# mini_controller_m328.net
KiCad netlist of a schematic drawn in EAGLE
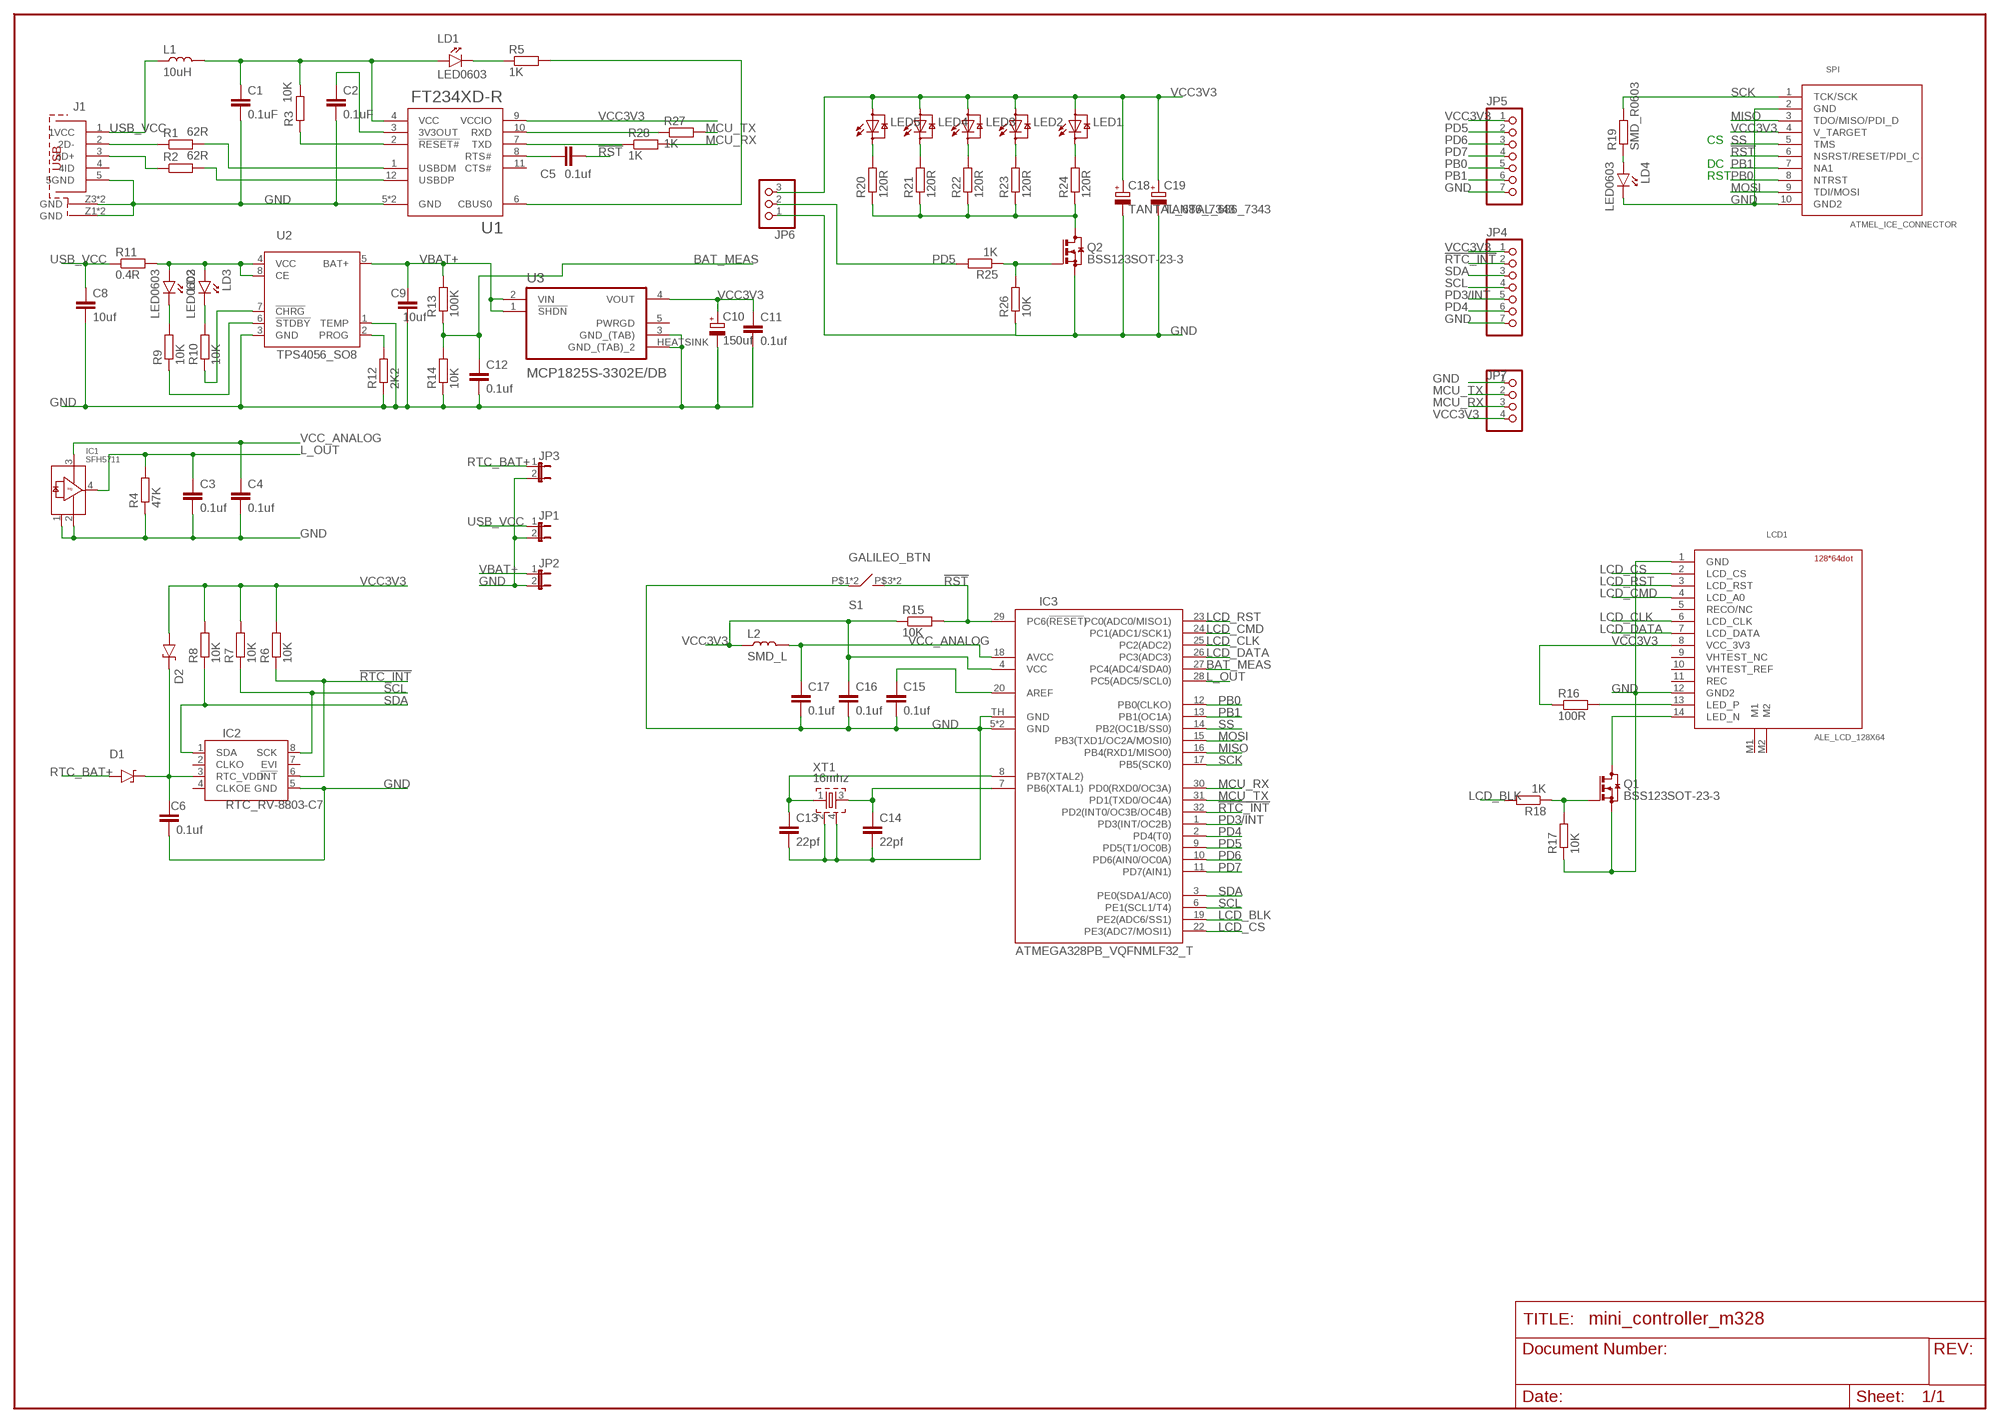
[diagram p0: schematic, sheet 1]

(export (version "E")
  (design (tool "Eeschema 10.0.6"))
  (components
    (comp (ref "C1")
      (value "0.1uF")
      (footprint "eagle-import:0603")
      (libsource (lib "eagle-import") (part "SMD_C0603"))
    )
    (comp (ref "C2")
      (value "0.1uF")
      (footprint "eagle-import:0603")
      (libsource (lib "eagle-import") (part "SMD_C0603"))
    )
    (comp (ref "C3")
      (value "0.1uf")
      (footprint "eagle-import:0603")
      (libsource (lib "eagle-import") (part "SMD_C0603"))
    )
    (comp (ref "C4")
      (value "0.1uf")
      (footprint "eagle-import:0603")
      (libsource (lib "eagle-import") (part "SMD_C0603"))
    )
    (comp (ref "C5")
      (value "0.1uf")
      (footprint "eagle-import:0603")
      (libsource (lib "eagle-import") (part "SMD_C0603"))
    )
    (comp (ref "C6")
      (value "0.1uf")
      (footprint "eagle-import:0603")
      (libsource (lib "eagle-import") (part "SMD_C0603"))
    )
    (comp (ref "C8")
      (value "10uf")
      (footprint "eagle-import:1206")
      (libsource (lib "eagle-import") (part "SMD_C1206"))
    )
    (comp (ref "C9")
      (value "10uf")
      (footprint "eagle-import:1206")
      (libsource (lib "eagle-import") (part "SMD_C1206"))
    )
    (comp (ref "C10")
      (value "150uf")
      (footprint "eagle-import:KA-3528ASYC")
      (libsource (lib "eagle-import") (part "TANTAL_150UF_3528"))
    )
    (comp (ref "C11")
      (value "0.1uf")
      (footprint "eagle-import:0603")
      (libsource (lib "eagle-import") (part "SMD_C0603"))
    )
    (comp (ref "C12")
      (value "0.1uf")
      (footprint "eagle-import:0603")
      (libsource (lib "eagle-import") (part "SMD_C0603"))
    )
    (comp (ref "C13")
      (value "22pf")
      (footprint "eagle-import:0603")
      (libsource (lib "eagle-import") (part "SMD_C0603"))
    )
    (comp (ref "C14")
      (value "22pf")
      (footprint "eagle-import:0603")
      (libsource (lib "eagle-import") (part "SMD_C0603"))
    )
    (comp (ref "C15")
      (value "0.1uf")
      (footprint "eagle-import:0603")
      (libsource (lib "eagle-import") (part "SMD_C0603"))
    )
    (comp (ref "C16")
      (value "0.1uf")
      (footprint "eagle-import:0603")
      (libsource (lib "eagle-import") (part "SMD_C0603"))
    )
    (comp (ref "C17")
      (value "0.1uf")
      (footprint "eagle-import:0603")
      (libsource (lib "eagle-import") (part "SMD_C0603"))
    )
    (comp (ref "C18")
      (value "TANTAL_686_7343")
      (footprint "eagle-import:D_7343-31R")
      (libsource (lib "eagle-import") (part "TANTAL_686_7343"))
    )
    (comp (ref "C19")
      (value "TANTAL_686_7343")
      (footprint "eagle-import:D_7343-31R")
      (libsource (lib "eagle-import") (part "TANTAL_686_7343"))
    )
    (comp (ref "D1")
      (value "D_SOD323")
      (footprint "eagle-import:SOD-323_D")
      (libsource (lib "eagle-import") (part "D_SOD323"))
    )
    (comp (ref "D2")
      (value "D_SOD323")
      (footprint "eagle-import:SOD-323_D")
      (libsource (lib "eagle-import") (part "D_SOD323"))
    )
    (comp (ref "IC1")
      (value "SFH5711")
      (footprint "eagle-import:SFH5711")
      (fields (field (name "MF") "OSRAM Opto"))
      (libsource (lib "eagle-import") (part "SFH5711"))
    )
    (comp (ref "IC2")
      (value "RTC_RV-8803-C7")
      (footprint "eagle-import:C7_RTC")
      (libsource (lib "eagle-import") (part "RTC_RV-8803-C7"))
    )
    (comp (ref "IC3")
      (value "ATMEGA328PB_VQFNMLF32_T")
      (footprint "eagle-import:MLF32-TH")
      (libsource (lib "eagle-import") (part "ATMEGA328PB_VQFNMLF32_T"))
    )
    (comp (ref "J1")
      (value "MINI_USB_TYP_B_@")
      (footprint "eagle-import:65100516121")
      (libsource (lib "eagle-import") (part "MINI_USB_TYP_B_@"))
    )
    (comp (ref "JP1")
      (value "JP1E")
      (footprint "eagle-import:JP1")
      (libsource (lib "eagle-import") (part "JP1E"))
    )
    (comp (ref "JP2")
      (value "JP1E")
      (footprint "eagle-import:JP1")
      (libsource (lib "eagle-import") (part "JP1E"))
    )
    (comp (ref "JP3")
      (value "JP1E")
      (footprint "eagle-import:JP1")
      (libsource (lib "eagle-import") (part "JP1E"))
    )
    (comp (ref "JP4")
      (value "PINHD-1X7")
      (footprint "eagle-import:1X07")
      (libsource (lib "eagle-import") (part "PINHD-1X7"))
    )
    (comp (ref "JP5")
      (value "PINHD-1X7")
      (footprint "eagle-import:1X07")
      (libsource (lib "eagle-import") (part "PINHD-1X7"))
    )
    (comp (ref "JP6")
      (value "PINHD-1X3")
      (footprint "eagle-import:1X03")
      (libsource (lib "eagle-import") (part "PINHD-1X3"))
    )
    (comp (ref "JP7")
      (value "PINHD-1X4")
      (footprint "eagle-import:1X04")
      (libsource (lib "eagle-import") (part "PINHD-1X4"))
    )
    (comp (ref "L1")
      (value "10uH")
      (footprint "eagle-import:0805")
      (libsource (lib "eagle-import") (part "SMD_L"))
    )
    (comp (ref "L2")
      (value "SMD_L")
      (footprint "eagle-import:0805")
      (libsource (lib "eagle-import") (part "SMD_L"))
    )
    (comp (ref "LCD1")
      (value "ALE_LCD_128X64")
      (footprint "eagle-import:ALE_LCD_14PIN_CONNECTOR")
      (libsource (lib "eagle-import") (part "ALE_LCD_128X64"))
    )
    (comp (ref "LD1")
      (value "LED0603")
      (footprint "eagle-import:0603_P")
      (libsource (lib "eagle-import") (part "LED0603"))
    )
    (comp (ref "LD2")
      (value "LED0603")
      (footprint "eagle-import:0603_P")
      (libsource (lib "eagle-import") (part "LED0603"))
    )
    (comp (ref "LD3")
      (value "LED0603")
      (footprint "eagle-import:0603_P")
      (libsource (lib "eagle-import") (part "LED0603"))
    )
    (comp (ref "LD4")
      (value "LED0603")
      (footprint "eagle-import:0603_P")
      (libsource (lib "eagle-import") (part "LED0603"))
    )
    (comp (ref "LED1")
      (value "GM5BW96385A")
      (footprint "eagle-import:GM5BW96385A")
      (libsource (lib "eagle-import") (part "GM5BW96385A"))
    )
    (comp (ref "LED2")
      (value "GM5BW96385A")
      (footprint "eagle-import:GM5BW96385A")
      (libsource (lib "eagle-import") (part "GM5BW96385A"))
    )
    (comp (ref "LED3")
      (value "GM5BW96385A")
      (footprint "eagle-import:GM5BW96385A")
      (libsource (lib "eagle-import") (part "GM5BW96385A"))
    )
    (comp (ref "LED4")
      (value "GM5BW96385A")
      (footprint "eagle-import:GM5BW96385A")
      (libsource (lib "eagle-import") (part "GM5BW96385A"))
    )
    (comp (ref "LED5")
      (value "GM5BW96385A")
      (footprint "eagle-import:GM5BW96385A")
      (libsource (lib "eagle-import") (part "GM5BW96385A"))
    )
    (comp (ref "Q1")
      (value "BSS123SOT-23-3")
      (footprint "eagle-import:SOT-23(3)")
      (libsource (lib "eagle-import") (part "BSS123SOT-23-3"))
    )
    (comp (ref "Q2")
      (value "BSS123SOT-23-3")
      (footprint "eagle-import:SOT-23(3)")
      (libsource (lib "eagle-import") (part "BSS123SOT-23-3"))
    )
    (comp (ref "R1")
      (value "62R")
      (footprint "eagle-import:0603")
      (libsource (lib "eagle-import") (part "SMD_R0603"))
    )
    (comp (ref "R2")
      (value "62R")
      (footprint "eagle-import:0603")
      (libsource (lib "eagle-import") (part "SMD_R0603"))
    )
    (comp (ref "R3")
      (value "10K")
      (footprint "eagle-import:0603")
      (libsource (lib "eagle-import") (part "SMD_R0603"))
    )
    (comp (ref "R4")
      (value "47K")
      (footprint "eagle-import:0603")
      (libsource (lib "eagle-import") (part "SMD_R0603"))
    )
    (comp (ref "R5")
      (value "1K")
      (footprint "eagle-import:0603")
      (libsource (lib "eagle-import") (part "SMD_R0603"))
    )
    (comp (ref "R6")
      (value "10K")
      (footprint "eagle-import:0603")
      (libsource (lib "eagle-import") (part "SMD_R0603"))
    )
    (comp (ref "R7")
      (value "10K")
      (footprint "eagle-import:0603")
      (libsource (lib "eagle-import") (part "SMD_R0603"))
    )
    (comp (ref "R8")
      (value "10K")
      (footprint "eagle-import:0603")
      (libsource (lib "eagle-import") (part "SMD_R0603"))
    )
    (comp (ref "R9")
      (value "10K")
      (footprint "eagle-import:0603")
      (libsource (lib "eagle-import") (part "SMD_R0603"))
    )
    (comp (ref "R10")
      (value "10K")
      (footprint "eagle-import:0603")
      (libsource (lib "eagle-import") (part "SMD_R0603"))
    )
    (comp (ref "R11")
      (value "0.4R")
      (footprint "eagle-import:1206")
      (libsource (lib "eagle-import") (part "SMD_R1206"))
    )
    (comp (ref "R12")
      (value "2K2")
      (footprint "eagle-import:0603")
      (libsource (lib "eagle-import") (part "SMD_R0603"))
    )
    (comp (ref "R13")
      (value "100K")
      (footprint "eagle-import:0603")
      (libsource (lib "eagle-import") (part "SMD_R0603"))
    )
    (comp (ref "R14")
      (value "10K")
      (footprint "eagle-import:0603")
      (libsource (lib "eagle-import") (part "SMD_R0603"))
    )
    (comp (ref "R15")
      (value "10K")
      (footprint "eagle-import:0603")
      (libsource (lib "eagle-import") (part "SMD_R0603"))
    )
    (comp (ref "R16")
      (value "100R")
      (footprint "eagle-import:0603")
      (libsource (lib "eagle-import") (part "SMD_R0603"))
    )
    (comp (ref "R17")
      (value "10K")
      (footprint "eagle-import:0603")
      (libsource (lib "eagle-import") (part "SMD_R0603"))
    )
    (comp (ref "R18")
      (value "1K")
      (footprint "eagle-import:0603")
      (libsource (lib "eagle-import") (part "SMD_R0603"))
    )
    (comp (ref "R19")
      (value "SMD_R0603")
      (footprint "eagle-import:0603")
      (libsource (lib "eagle-import") (part "SMD_R0603"))
    )
    (comp (ref "R20")
      (value "120R")
      (footprint "eagle-import:1206")
      (libsource (lib "eagle-import") (part "SMD_R1206"))
    )
    (comp (ref "R21")
      (value "120R")
      (footprint "eagle-import:1206")
      (libsource (lib "eagle-import") (part "SMD_R1206"))
    )
    (comp (ref "R22")
      (value "120R")
      (footprint "eagle-import:1206")
      (libsource (lib "eagle-import") (part "SMD_R1206"))
    )
    (comp (ref "R23")
      (value "120R")
      (footprint "eagle-import:1206")
      (libsource (lib "eagle-import") (part "SMD_R1206"))
    )
    (comp (ref "R24")
      (value "120R")
      (footprint "eagle-import:1206")
      (libsource (lib "eagle-import") (part "SMD_R1206"))
    )
    (comp (ref "R25")
      (value "1K")
      (footprint "eagle-import:0603")
      (libsource (lib "eagle-import") (part "SMD_R0603"))
    )
    (comp (ref "R26")
      (value "10K")
      (footprint "eagle-import:0603")
      (libsource (lib "eagle-import") (part "SMD_R0603"))
    )
    (comp (ref "R27")
      (value "1K")
      (footprint "eagle-import:0603")
      (libsource (lib "eagle-import") (part "SMD_R0603"))
    )
    (comp (ref "R28")
      (value "1K")
      (footprint "eagle-import:0603")
      (libsource (lib "eagle-import") (part "SMD_R0603"))
    )
    (comp (ref "S1")
      (value "GALILEO_BTN")
      (footprint "eagle-import:GALILEO_VERT_BTN")
      (libsource (lib "eagle-import") (part "GALILEO_BTN"))
    )
    (comp (ref "SPI")
      (value "ATMEL_ICE_CONNECTOR")
      (footprint "eagle-import:MINI10P_SPI_JTAG_PDI")
      (libsource (lib "eagle-import") (part "ATMEL_ICE_CONNECTOR"))
    )
    (comp (ref "U1")
      (value "FT234XD-R")
      (footprint "eagle-import:IC_FT234XD-R")
      (fields (field (name "MF") "FTDI,"))
      (libsource (lib "eagle-import") (part "FT234XD-R"))
    )
    (comp (ref "U2")
      (value "TPS4056_SO8")
      (footprint "eagle-import:SO8")
      (libsource (lib "eagle-import") (part "TPS4056_SO8"))
    )
    (comp (ref "U3")
      (value "MCP1825S-3302E/DB")
      (footprint "eagle-import:SOT230P700X180-4N")
      (fields (field (name "MF") "Microchip"))
      (libsource (lib "eagle-import") (part "MCP1825S-3302E/DB"))
    )
    (comp (ref "XT1")
      (value "16mhz")
      (footprint "eagle-import:QUARTZ_3X3MM")
      (libsource (lib "eagle-import") (part "QUARTZ_ZQ"))
    )
  )
  (nets
    (net (code "1") (name "/BAT_MEAS") (class "Default")
      (node (ref "C12") (pin "1") (pinfunction "1_1") (pintype "passive"))
      (node (ref "IC3") (pin "27") (pinfunction "PC4(ADC4/SDA0)_27") (pintype "bidirectional"))
      (node (ref "R13") (pin "1") (pinfunction "1_1") (pintype "passive"))
      (node (ref "R14") (pin "2") (pinfunction "2_2") (pintype "passive"))
    )
    (net (code "2") (name "/GND") (class "Default")
      (node (ref "C1") (pin "2") (pinfunction "2_2") (pintype "passive"))
      (node (ref "C10") (pin "M") (pinfunction "-_M") (pintype "passive"))
      (node (ref "C11") (pin "2") (pinfunction "2_2") (pintype "passive"))
      (node (ref "C12") (pin "2") (pinfunction "2_2") (pintype "passive"))
      (node (ref "C13") (pin "2") (pinfunction "2_2") (pintype "passive"))
      (node (ref "C14") (pin "2") (pinfunction "2_2") (pintype "passive"))
      (node (ref "C15") (pin "2") (pinfunction "2_2") (pintype "passive"))
      (node (ref "C16") (pin "2") (pinfunction "2_2") (pintype "passive"))
      (node (ref "C17") (pin "2") (pinfunction "2_2") (pintype "passive"))
      (node (ref "C18") (pin "-") (pinfunction "-_-") (pintype "passive"))
      (node (ref "C19") (pin "-") (pinfunction "-_-") (pintype "passive"))
      (node (ref "C2") (pin "2") (pinfunction "2_2") (pintype "passive"))
      (node (ref "C3") (pin "2") (pinfunction "2_2") (pintype "passive"))
      (node (ref "C4") (pin "2") (pinfunction "2_2") (pintype "passive"))
      (node (ref "C6") (pin "2") (pinfunction "2_2") (pintype "passive"))
      (node (ref "C8") (pin "2") (pinfunction "2_2") (pintype "passive"))
      (node (ref "C9") (pin "2") (pinfunction "2_2") (pintype "passive"))
      (node (ref "IC1") (pin "1") (pinfunction "1_1") (pintype "bidirectional"))
      (node (ref "IC1") (pin "2") (pinfunction "2_2") (pintype "bidirectional"))
      (node (ref "IC2") (pin "5") (pinfunction "GND_5") (pintype "bidirectional"))
      (node (ref "IC3") (pin "21") (pinfunction "GND_21") (pintype "power_in"))
      (node (ref "IC3") (pin "5") (pinfunction "GND_5") (pintype "power_in"))
      (node (ref "IC3") (pin "TH") (pinfunction "GND_TH") (pintype "power_in"))
      (node (ref "J1") (pin "5") (pinfunction "5GND_5") (pintype "passive"))
      (node (ref "J1") (pin "Z1") (pinfunction "GND_Z1") (pintype "bidirectional"))
      (node (ref "J1") (pin "Z2") (pinfunction "GND_Z2") (pintype "bidirectional"))
      (node (ref "J1") (pin "Z3") (pinfunction "GND_Z3") (pintype "bidirectional"))
      (node (ref "J1") (pin "Z4") (pinfunction "GND_Z4") (pintype "bidirectional"))
      (node (ref "JP1") (pin "2") (pinfunction "2_2") (pintype "passive"))
      (node (ref "JP2") (pin "2") (pinfunction "2_2") (pintype "passive"))
      (node (ref "JP3") (pin "2") (pinfunction "2_2") (pintype "passive"))
      (node (ref "JP4") (pin "7") (pinfunction "7_7") (pintype "passive"))
      (node (ref "JP5") (pin "7") (pinfunction "7_7") (pintype "passive"))
      (node (ref "JP6") (pin "1") (pinfunction "1_1") (pintype "passive"))
      (node (ref "JP7") (pin "1") (pinfunction "1_1") (pintype "passive"))
      (node (ref "LCD1") (pin "1") (pinfunction "GND_1") (pintype "bidirectional"))
      (node (ref "LCD1") (pin "12") (pinfunction "GND2_12") (pintype "bidirectional"))
      (node (ref "LD4") (pin "1") (pinfunction "K_1") (pintype "bidirectional"))
      (node (ref "Q1") (pin "2") (pinfunction "S_2") (pintype "passive"))
      (node (ref "Q2") (pin "2") (pinfunction "S_2") (pintype "passive"))
      (node (ref "R12") (pin "1") (pinfunction "1_1") (pintype "passive"))
      (node (ref "R14") (pin "1") (pinfunction "1_1") (pintype "passive"))
      (node (ref "R17") (pin "1") (pinfunction "1_1") (pintype "passive"))
      (node (ref "R26") (pin "1") (pinfunction "1_1") (pintype "passive"))
      (node (ref "R4") (pin "1") (pinfunction "1_1") (pintype "passive"))
      (node (ref "S1") (pin "P$1") (pinfunction "1_P$1") (pintype "bidirectional"))
      (node (ref "S1") (pin "P$2") (pinfunction "1_P$2") (pintype "bidirectional"))
      (node (ref "SPI") (pin "10") (pinfunction "GND2_10") (pintype "bidirectional"))
      (node (ref "SPI") (pin "2") (pinfunction "GND_2") (pintype "bidirectional"))
      (node (ref "U1") (pin "13") (pinfunction "GND_13") (pintype "power_in"))
      (node (ref "U1") (pin "5") (pinfunction "GND_5") (pintype "power_in"))
      (node (ref "U2") (pin "1") (pinfunction "TEMP_1") (pintype "bidirectional"))
      (node (ref "U2") (pin "3") (pinfunction "GND_3") (pintype "bidirectional"))
      (node (ref "U3") (pin "3") (pinfunction "GND_(TAB)_3") (pintype "power_in"))
      (node (ref "U3") (pin "HEATSINK") (pinfunction "GND_(TAB)_2_HEATSINK") (pintype "power_in"))
      (node (ref "XT1") (pin "2") (pinfunction "2_2") (pintype "passive"))
      (node (ref "XT1") (pin "4") (pinfunction "4_4") (pintype "passive"))
    )
    (net (code "3") (name "/LCD_BLK") (class "Default")
      (node (ref "IC3") (pin "19") (pinfunction "PE2(ADC6/SS1)_19") (pintype "bidirectional"))
      (node (ref "R18") (pin "2") (pinfunction "2_2") (pintype "passive"))
    )
    (net (code "4") (name "/LCD_CLK") (class "Default")
      (node (ref "IC3") (pin "25") (pinfunction "PC2(ADC2)_25") (pintype "bidirectional"))
      (node (ref "LCD1") (pin "6") (pinfunction "LCD_CLK_6") (pintype "bidirectional"))
    )
    (net (code "5") (name "/LCD_CMD") (class "Default")
      (node (ref "IC3") (pin "24") (pinfunction "PC1(ADC1/SCK1)_24") (pintype "bidirectional"))
      (node (ref "LCD1") (pin "4") (pinfunction "LCD_A0_4") (pintype "bidirectional"))
    )
    (net (code "6") (name "/LCD_CS") (class "Default")
      (node (ref "IC3") (pin "22") (pinfunction "PE3(ADC7/MOSI1)_22") (pintype "bidirectional"))
      (node (ref "LCD1") (pin "2") (pinfunction "LCD_CS_2") (pintype "bidirectional"))
    )
    (net (code "7") (name "/LCD_DATA") (class "Default")
      (node (ref "IC3") (pin "26") (pinfunction "PC3(ADC3)_26") (pintype "bidirectional"))
      (node (ref "LCD1") (pin "7") (pinfunction "LCD_DATA_7") (pintype "bidirectional"))
    )
    (net (code "8") (name "/LCD_RST") (class "Default")
      (node (ref "IC3") (pin "23") (pinfunction "PC0(ADC0/MISO1)_23") (pintype "bidirectional"))
      (node (ref "LCD1") (pin "3") (pinfunction "LCD_RST_3") (pintype "bidirectional"))
    )
    (net (code "9") (name "/L_OUT") (class "Default")
      (node (ref "C3") (pin "1") (pinfunction "1_1") (pintype "passive"))
      (node (ref "IC1") (pin "4") (pinfunction "4_4") (pintype "bidirectional"))
      (node (ref "IC3") (pin "28") (pinfunction "PC5(ADC5/SCL0)_28") (pintype "bidirectional"))
      (node (ref "R4") (pin "2") (pinfunction "2_2") (pintype "passive"))
    )
    (net (code "10") (name "/MCU_RX") (class "Default")
      (node (ref "IC3") (pin "30") (pinfunction "PD0(RXD0/OC3A)_30") (pintype "bidirectional"))
      (node (ref "JP7") (pin "3") (pinfunction "3_3") (pintype "passive"))
      (node (ref "R28") (pin "2") (pinfunction "2_2") (pintype "passive"))
    )
    (net (code "11") (name "/MCU_TX") (class "Default")
      (node (ref "IC3") (pin "31") (pinfunction "PD1(TXD0/OC4A)_31") (pintype "bidirectional"))
      (node (ref "JP7") (pin "2") (pinfunction "2_2") (pintype "passive"))
      (node (ref "R27") (pin "2") (pinfunction "2_2") (pintype "passive"))
    )
    (net (code "12") (name "/MISO") (class "Default")
      (node (ref "IC3") (pin "16") (pinfunction "PB4(RXD1/MISO0)_16") (pintype "bidirectional"))
      (node (ref "SPI") (pin "3") (pinfunction "TDO/MISO/PDI_D_3") (pintype "bidirectional"))
    )
    (net (code "13") (name "/MOSI") (class "Default")
      (node (ref "IC3") (pin "15") (pinfunction "PB3(TXD1/OC2A/MOSI0)_15") (pintype "bidirectional"))
      (node (ref "SPI") (pin "9") (pinfunction "TDI/MOSI_9") (pintype "bidirectional"))
    )
    (net (code "14") (name "/PB0") (class "Default")
      (node (ref "IC3") (pin "12") (pinfunction "PB0(CLKO)_12") (pintype "bidirectional"))
      (node (ref "JP5") (pin "5") (pinfunction "5_5") (pintype "passive"))
      (node (ref "SPI") (pin "8") (pinfunction "NTRST_8") (pintype "bidirectional"))
    )
    (net (code "15") (name "/PB1") (class "Default")
      (node (ref "IC3") (pin "13") (pinfunction "PB1(OC1A)_13") (pintype "bidirectional"))
      (node (ref "JP5") (pin "6") (pinfunction "6_6") (pintype "passive"))
      (node (ref "SPI") (pin "7") (pinfunction "NA1_7") (pintype "bidirectional"))
    )
    (net (code "16") (name "/PD3{slash}INT") (class "Default")
      (node (ref "IC3") (pin "1") (pinfunction "PD3(INT/OC2B)_1") (pintype "bidirectional"))
      (node (ref "JP4") (pin "5") (pinfunction "5_5") (pintype "passive"))
    )
    (net (code "17") (name "/PD4") (class "Default")
      (node (ref "IC3") (pin "2") (pinfunction "PD4(T0)_2") (pintype "bidirectional"))
      (node (ref "JP4") (pin "6") (pinfunction "6_6") (pintype "passive"))
    )
    (net (code "18") (name "/PD5") (class "Default")
      (node (ref "IC3") (pin "9") (pinfunction "PD5(T1/OC0B)_9") (pintype "bidirectional"))
      (node (ref "JP5") (pin "2") (pinfunction "2_2") (pintype "passive"))
      (node (ref "JP6") (pin "2") (pinfunction "2_2") (pintype "passive"))
      (node (ref "R25") (pin "2") (pinfunction "2_2") (pintype "passive"))
    )
    (net (code "19") (name "/PD6") (class "Default")
      (node (ref "IC3") (pin "10") (pinfunction "PD6(AIN0/OC0A)_10") (pintype "bidirectional"))
      (node (ref "JP5") (pin "3") (pinfunction "3_3") (pintype "passive"))
    )
    (net (code "20") (name "/PD7") (class "Default")
      (node (ref "IC3") (pin "11") (pinfunction "PD7(AIN1)_11") (pintype "bidirectional"))
      (node (ref "JP5") (pin "4") (pinfunction "4_4") (pintype "passive"))
    )
    (net (code "21") (name "/RTC_BAT+") (class "Default")
      (node (ref "D1") (pin "A") (pinfunction "A_A") (pintype "bidirectional"))
      (node (ref "JP3") (pin "1") (pinfunction "1_1") (pintype "passive"))
    )
    (net (code "22") (name "/SCK") (class "Default")
      (node (ref "IC3") (pin "17") (pinfunction "PB5(SCK0)_17") (pintype "bidirectional"))
      (node (ref "R19") (pin "2") (pinfunction "2_2") (pintype "passive"))
      (node (ref "SPI") (pin "1") (pinfunction "TCK/SCK_1") (pintype "bidirectional"))
    )
    (net (code "23") (name "/SCL") (class "Default")
      (node (ref "IC2") (pin "8") (pinfunction "SCK_8") (pintype "bidirectional"))
      (node (ref "IC3") (pin "6") (pinfunction "PE1(SCL1/T4)_6") (pintype "bidirectional"))
      (node (ref "JP4") (pin "4") (pinfunction "4_4") (pintype "passive"))
      (node (ref "R7") (pin "1") (pinfunction "1_1") (pintype "passive"))
    )
    (net (code "24") (name "/SDA") (class "Default")
      (node (ref "IC2") (pin "1") (pinfunction "SDA_1") (pintype "bidirectional"))
      (node (ref "IC3") (pin "3") (pinfunction "PE0(SDA1/AC0)_3") (pintype "bidirectional"))
      (node (ref "JP4") (pin "3") (pinfunction "3_3") (pintype "passive"))
      (node (ref "R8") (pin "1") (pinfunction "1_1") (pintype "passive"))
    )
    (net (code "25") (name "/SS") (class "Default")
      (node (ref "IC3") (pin "14") (pinfunction "PB2(OC1B/SS0)_14") (pintype "bidirectional"))
      (node (ref "SPI") (pin "5") (pinfunction "TMS_5") (pintype "bidirectional"))
    )
    (net (code "26") (name "/USB_VCC") (class "Default")
      (node (ref "C8") (pin "1") (pinfunction "1_1") (pintype "passive"))
      (node (ref "J1") (pin "1") (pinfunction "1VCC_1") (pintype "passive"))
      (node (ref "JP1") (pin "1") (pinfunction "1_1") (pintype "passive"))
      (node (ref "L1") (pin "1") (pinfunction "1_1") (pintype "passive"))
      (node (ref "R11") (pin "1") (pinfunction "1_1") (pintype "passive"))
    )
    (net (code "27") (name "/VBAT+") (class "Default")
      (node (ref "C9") (pin "1") (pinfunction "1_1") (pintype "passive"))
      (node (ref "JP2") (pin "1") (pinfunction "1_1") (pintype "passive"))
      (node (ref "R13") (pin "2") (pinfunction "2_2") (pintype "passive"))
      (node (ref "U2") (pin "5") (pinfunction "BAT+_5") (pintype "bidirectional"))
      (node (ref "U3") (pin "1") (pinfunction "~{SHDN}_1") (pintype "bidirectional"))
      (node (ref "U3") (pin "2") (pinfunction "VIN_2") (pintype "input"))
    )
    (net (code "28") (name "/VCC3V3") (class "Default")
      (node (ref "C10") (pin "P") (pinfunction "+_P") (pintype "passive"))
      (node (ref "C11") (pin "1") (pinfunction "1_1") (pintype "passive"))
      (node (ref "C16") (pin "1") (pinfunction "1_1") (pintype "passive"))
      (node (ref "C18") (pin "+") (pinfunction "+_+") (pintype "passive"))
      (node (ref "C19") (pin "+") (pinfunction "+_+") (pintype "passive"))
      (node (ref "D2") (pin "A") (pinfunction "A_A") (pintype "bidirectional"))
      (node (ref "IC3") (pin "4") (pinfunction "VCC_4") (pintype "power_in"))
      (node (ref "JP4") (pin "1") (pinfunction "1_1") (pintype "passive"))
      (node (ref "JP5") (pin "1") (pinfunction "1_1") (pintype "passive"))
      (node (ref "JP6") (pin "3") (pinfunction "3_3") (pintype "passive"))
      (node (ref "JP7") (pin "4") (pinfunction "4_4") (pintype "passive"))
      (node (ref "L2") (pin "1") (pinfunction "1_1") (pintype "passive"))
      (node (ref "LCD1") (pin "8") (pinfunction "VCC_3V3_8") (pintype "bidirectional"))
      (node (ref "LED1") (pin "A") (pinfunction "A_A") (pintype "passive"))
      (node (ref "LED2") (pin "A") (pinfunction "A_A") (pintype "passive"))
      (node (ref "LED3") (pin "A") (pinfunction "A_A") (pintype "passive"))
      (node (ref "LED4") (pin "A") (pinfunction "A_A") (pintype "passive"))
      (node (ref "LED5") (pin "A") (pinfunction "A_A") (pintype "passive"))
      (node (ref "R15") (pin "1") (pinfunction "1_1") (pintype "passive"))
      (node (ref "R16") (pin "1") (pinfunction "1_1") (pintype "passive"))
      (node (ref "R6") (pin "2") (pinfunction "2_2") (pintype "passive"))
      (node (ref "R7") (pin "2") (pinfunction "2_2") (pintype "passive"))
      (node (ref "R8") (pin "2") (pinfunction "2_2") (pintype "passive"))
      (node (ref "SPI") (pin "4") (pinfunction "V_TARGET_4") (pintype "bidirectional"))
      (node (ref "U1") (pin "9") (pinfunction "VCCIO_9") (pintype "power_in"))
      (node (ref "U3") (pin "4") (pinfunction "VOUT_4") (pintype "output"))
    )
    (net (code "29") (name "/VCC_ANALOG") (class "Default")
      (node (ref "C17") (pin "1") (pinfunction "1_1") (pintype "passive"))
      (node (ref "C4") (pin "1") (pinfunction "1_1") (pintype "passive"))
      (node (ref "IC1") (pin "3") (pinfunction "3_3") (pintype "bidirectional"))
      (node (ref "IC3") (pin "18") (pinfunction "AVCC_18") (pintype "power_in"))
      (node (ref "L2") (pin "2") (pinfunction "2_2") (pintype "passive"))
    )
    (net (code "30") (name "/~{RST}") (class "Default")
      (node (ref "C5") (pin "2") (pinfunction "2_2") (pintype "passive"))
      (node (ref "IC3") (pin "29") (pinfunction "PC6(~{RESET})_29") (pintype "bidirectional"))
      (node (ref "R15") (pin "2") (pinfunction "2_2") (pintype "passive"))
      (node (ref "S1") (pin "P$3") (pinfunction "4_P$3") (pintype "bidirectional"))
      (node (ref "S1") (pin "P$4") (pinfunction "4_P$4") (pintype "bidirectional"))
      (node (ref "SPI") (pin "6") (pinfunction "NSRST/RESET/PDI_C_6") (pintype "bidirectional"))
    )
    (net (code "31") (name "/~{RTC_INT}") (class "Default")
      (node (ref "IC2") (pin "6") (pinfunction "~{INT}_6") (pintype "bidirectional"))
      (node (ref "IC3") (pin "32") (pinfunction "PD2(INT0/OC3B/OC4B)_32") (pintype "bidirectional"))
      (node (ref "JP4") (pin "2") (pinfunction "2_2") (pintype "passive"))
      (node (ref "R6") (pin "1") (pinfunction "1_1") (pintype "passive"))
    )
    (net (code "32") (name "Net-(IC2-RTC_VDD)") (class "Default")
      (node (ref "C6") (pin "1") (pinfunction "1_1") (pintype "passive"))
      (node (ref "D1") (pin "K") (pinfunction "K_K") (pintype "bidirectional"))
      (node (ref "D2") (pin "K") (pinfunction "K_K") (pintype "bidirectional"))
      (node (ref "IC2") (pin "3") (pinfunction "RTC_VDD_3") (pintype "bidirectional"))
    )
    (net (code "33") (name "Net-(IC3-AREF)") (class "Default")
      (node (ref "C15") (pin "1") (pinfunction "1_1") (pintype "passive"))
      (node (ref "IC3") (pin "20") (pinfunction "AREF_20") (pintype "passive"))
    )
    (net (code "34") (name "Net-(IC3-PB6(XTAL1))") (class "Default")
      (node (ref "C14") (pin "1") (pinfunction "1_1") (pintype "passive"))
      (node (ref "IC3") (pin "7") (pinfunction "PB6(XTAL1)_7") (pintype "bidirectional"))
      (node (ref "XT1") (pin "3") (pinfunction "3_3") (pintype "passive"))
    )
    (net (code "35") (name "Net-(IC3-PB7(XTAL2))") (class "Default")
      (node (ref "C13") (pin "1") (pinfunction "1_1") (pintype "passive"))
      (node (ref "IC3") (pin "8") (pinfunction "PB7(XTAL2)_8") (pintype "bidirectional"))
      (node (ref "XT1") (pin "1") (pinfunction "1_1") (pintype "passive"))
    )
    (net (code "36") (name "Net-(J1-2D-)") (class "Default")
      (node (ref "J1") (pin "2") (pinfunction "2D-_2") (pintype "passive"))
      (node (ref "R1") (pin "1") (pinfunction "1_1") (pintype "passive"))
    )
    (net (code "37") (name "Net-(J1-3D+)") (class "Default")
      (node (ref "J1") (pin "3") (pinfunction "3D+_3") (pintype "passive"))
      (node (ref "R2") (pin "1") (pinfunction "1_1") (pintype "passive"))
    )
    (net (code "38") (name "Net-(LCD1-LED_N)") (class "Default")
      (node (ref "LCD1") (pin "14") (pinfunction "LED_N_14") (pintype "bidirectional"))
      (node (ref "Q1") (pin "3") (pinfunction "D_3") (pintype "passive"))
    )
    (net (code "39") (name "Net-(LCD1-LED_P)") (class "Default")
      (node (ref "LCD1") (pin "13") (pinfunction "LED_P_13") (pintype "bidirectional"))
      (node (ref "R16") (pin "2") (pinfunction "2_2") (pintype "passive"))
    )
    (net (code "40") (name "Net-(LD1-A)") (class "Default")
      (node (ref "C1") (pin "1") (pinfunction "1_1") (pintype "passive"))
      (node (ref "L1") (pin "2") (pinfunction "2_2") (pintype "passive"))
      (node (ref "LD1") (pin "2") (pinfunction "A_2") (pintype "bidirectional"))
      (node (ref "R3") (pin "2") (pinfunction "2_2") (pintype "passive"))
      (node (ref "U1") (pin "4") (pinfunction "VCC_4") (pintype "power_in"))
    )
    (net (code "41") (name "Net-(LD1-K)") (class "Default")
      (node (ref "LD1") (pin "1") (pinfunction "K_1") (pintype "bidirectional"))
      (node (ref "R5") (pin "1") (pinfunction "1_1") (pintype "passive"))
    )
    (net (code "42") (name "Net-(LD2-A)") (class "Default")
      (node (ref "LD2") (pin "2") (pinfunction "A_2") (pintype "bidirectional"))
      (node (ref "LD3") (pin "2") (pinfunction "A_2") (pintype "bidirectional"))
      (node (ref "R11") (pin "2") (pinfunction "2_2") (pintype "passive"))
      (node (ref "U2") (pin "4") (pinfunction "VCC_4") (pintype "bidirectional"))
      (node (ref "U2") (pin "8") (pinfunction "CE_8") (pintype "bidirectional"))
    )
    (net (code "43") (name "Net-(LD2-K)") (class "Default")
      (node (ref "LD2") (pin "1") (pinfunction "K_1") (pintype "bidirectional"))
      (node (ref "R9") (pin "2") (pinfunction "2_2") (pintype "passive"))
    )
    (net (code "44") (name "Net-(LD3-K)") (class "Default")
      (node (ref "LD3") (pin "1") (pinfunction "K_1") (pintype "bidirectional"))
      (node (ref "R10") (pin "2") (pinfunction "2_2") (pintype "passive"))
    )
    (net (code "45") (name "Net-(LD4-A)") (class "Default")
      (node (ref "LD4") (pin "2") (pinfunction "A_2") (pintype "bidirectional"))
      (node (ref "R19") (pin "1") (pinfunction "1_1") (pintype "passive"))
    )
    (net (code "46") (name "Net-(LED1-PadC)") (class "Default")
      (node (ref "LED1") (pin "C") (pinfunction "C_C") (pintype "passive"))
      (node (ref "R24") (pin "2") (pinfunction "2_2") (pintype "passive"))
    )
    (net (code "47") (name "Net-(LED2-PadC)") (class "Default")
      (node (ref "LED2") (pin "C") (pinfunction "C_C") (pintype "passive"))
      (node (ref "R23") (pin "2") (pinfunction "2_2") (pintype "passive"))
    )
    (net (code "48") (name "Net-(LED3-PadC)") (class "Default")
      (node (ref "LED3") (pin "C") (pinfunction "C_C") (pintype "passive"))
      (node (ref "R22") (pin "2") (pinfunction "2_2") (pintype "passive"))
    )
    (net (code "49") (name "Net-(LED4-PadC)") (class "Default")
      (node (ref "LED4") (pin "C") (pinfunction "C_C") (pintype "passive"))
      (node (ref "R21") (pin "2") (pinfunction "2_2") (pintype "passive"))
    )
    (net (code "50") (name "Net-(LED5-PadC)") (class "Default")
      (node (ref "LED5") (pin "C") (pinfunction "C_C") (pintype "passive"))
      (node (ref "R20") (pin "2") (pinfunction "2_2") (pintype "passive"))
    )
    (net (code "51") (name "Net-(Q1-G)") (class "Default")
      (node (ref "Q1") (pin "1") (pinfunction "G_1") (pintype "passive"))
      (node (ref "R17") (pin "2") (pinfunction "2_2") (pintype "passive"))
      (node (ref "R18") (pin "1") (pinfunction "1_1") (pintype "passive"))
    )
    (net (code "52") (name "Net-(Q2-D)") (class "Default")
      (node (ref "Q2") (pin "3") (pinfunction "D_3") (pintype "passive"))
      (node (ref "R20") (pin "1") (pinfunction "1_1") (pintype "passive"))
      (node (ref "R21") (pin "1") (pinfunction "1_1") (pintype "passive"))
      (node (ref "R22") (pin "1") (pinfunction "1_1") (pintype "passive"))
      (node (ref "R23") (pin "1") (pinfunction "1_1") (pintype "passive"))
      (node (ref "R24") (pin "1") (pinfunction "1_1") (pintype "passive"))
    )
    (net (code "53") (name "Net-(Q2-G)") (class "Default")
      (node (ref "Q2") (pin "1") (pinfunction "G_1") (pintype "passive"))
      (node (ref "R25") (pin "1") (pinfunction "1_1") (pintype "passive"))
      (node (ref "R26") (pin "2") (pinfunction "2_2") (pintype "passive"))
    )
    (net (code "54") (name "Net-(U1-3V3OUT)") (class "Default")
      (node (ref "C2") (pin "1") (pinfunction "1_1") (pintype "passive"))
      (node (ref "U1") (pin "3") (pinfunction "3V3OUT_3") (pintype "output"))
    )
    (net (code "55") (name "Net-(U1-CBUS0)") (class "Default")
      (node (ref "R5") (pin "2") (pinfunction "2_2") (pintype "passive"))
      (node (ref "U1") (pin "6") (pinfunction "CBUS0_6") (pintype "bidirectional"))
    )
    (net (code "56") (name "Net-(U1-RTS#)") (class "Default")
      (node (ref "C5") (pin "1") (pinfunction "1_1") (pintype "passive"))
      (node (ref "U1") (pin "8") (pinfunction "RTS#_8") (pintype "output"))
    )
    (net (code "57") (name "Net-(U1-RXD)") (class "Default")
      (node (ref "R27") (pin "1") (pinfunction "1_1") (pintype "passive"))
      (node (ref "U1") (pin "10") (pinfunction "RXD_10") (pintype "input"))
    )
    (net (code "58") (name "Net-(U1-TXD)") (class "Default")
      (node (ref "R28") (pin "1") (pinfunction "1_1") (pintype "passive"))
      (node (ref "U1") (pin "7") (pinfunction "TXD_7") (pintype "output"))
    )
    (net (code "59") (name "Net-(U1-USBDM)") (class "Default")
      (node (ref "R1") (pin "2") (pinfunction "2_2") (pintype "passive"))
      (node (ref "U1") (pin "1") (pinfunction "USBDM_1") (pintype "bidirectional"))
    )
    (net (code "60") (name "Net-(U1-USBDP)") (class "Default")
      (node (ref "R2") (pin "2") (pinfunction "2_2") (pintype "passive"))
      (node (ref "U1") (pin "12") (pinfunction "USBDP_12") (pintype "bidirectional"))
    )
    (net (code "61") (name "Net-(U1-~{RESET#})") (class "Default")
      (node (ref "R3") (pin "1") (pinfunction "1_1") (pintype "passive"))
      (node (ref "U1") (pin "2") (pinfunction "~{RESET#}_2") (pintype "input"))
    )
    (net (code "62") (name "Net-(U2-PROG)") (class "Default")
      (node (ref "R12") (pin "2") (pinfunction "2_2") (pintype "passive"))
      (node (ref "U2") (pin "2") (pinfunction "PROG_2") (pintype "bidirectional"))
    )
    (net (code "63") (name "Net-(U2-~{CHRG})") (class "Default")
      (node (ref "R10") (pin "1") (pinfunction "1_1") (pintype "passive"))
      (node (ref "U2") (pin "7") (pinfunction "~{CHRG}_7") (pintype "bidirectional"))
    )
    (net (code "64") (name "Net-(U2-~{STDBY})") (class "Default")
      (node (ref "R9") (pin "1") (pinfunction "1_1") (pintype "passive"))
      (node (ref "U2") (pin "6") (pinfunction "~{STDBY}_6") (pintype "bidirectional"))
    )
    (net (code "65") (name "unconnected-(IC2-CLKO-Pad2)") (class "Default")
      (node (ref "IC2") (pin "2") (pinfunction "CLKO_2") (pintype "bidirectional"))
    )
    (net (code "66") (name "unconnected-(IC2-CLKOE-Pad4)") (class "Default")
      (node (ref "IC2") (pin "4") (pinfunction "CLKOE_4") (pintype "bidirectional"))
    )
    (net (code "67") (name "unconnected-(IC2-EVI-Pad7)") (class "Default")
      (node (ref "IC2") (pin "7") (pinfunction "EVI_7") (pintype "bidirectional"))
    )
    (net (code "68") (name "unconnected-(J1-4ID-Pad4)") (class "Default")
      (node (ref "J1") (pin "4") (pinfunction "4ID_4") (pintype "passive"))
    )
    (net (code "69") (name "unconnected-(LCD1-PadM1)") (class "Default")
      (node (ref "LCD1") (pin "M1") (pinfunction "M1_M1") (pintype "bidirectional"))
    )
    (net (code "70") (name "unconnected-(LCD1-PadM2)") (class "Default")
      (node (ref "LCD1") (pin "M2") (pinfunction "M2_M2") (pintype "bidirectional"))
    )
    (net (code "71") (name "unconnected-(LCD1-REC-Pad11)") (class "Default")
      (node (ref "LCD1") (pin "11") (pinfunction "REC_11") (pintype "bidirectional"))
    )
    (net (code "72") (name "unconnected-(LCD1-RECO{slash}NC-Pad5)") (class "Default")
      (node (ref "LCD1") (pin "5") (pinfunction "RECO/NC_5") (pintype "bidirectional"))
    )
    (net (code "73") (name "unconnected-(LCD1-VHTEST_NC-Pad9)") (class "Default")
      (node (ref "LCD1") (pin "9") (pinfunction "VHTEST_NC_9") (pintype "bidirectional"))
    )
    (net (code "74") (name "unconnected-(LCD1-VHTEST_REF-Pad10)") (class "Default")
      (node (ref "LCD1") (pin "10") (pinfunction "VHTEST_REF_10") (pintype "bidirectional"))
    )
    (net (code "75") (name "unconnected-(U1-CTS#-Pad11)") (class "Default")
      (node (ref "U1") (pin "11") (pinfunction "CTS#_11") (pintype "input"))
    )
    (net (code "76") (name "unconnected-(U3-PWRGD-Pad5)") (class "Default")
      (node (ref "U3") (pin "5") (pinfunction "PWRGD_5") (pintype "bidirectional"))
    )
  )
)
